# 15-100M_ClkBuffer.net
KiCad netlist of a schematic drawn in Altium Designer
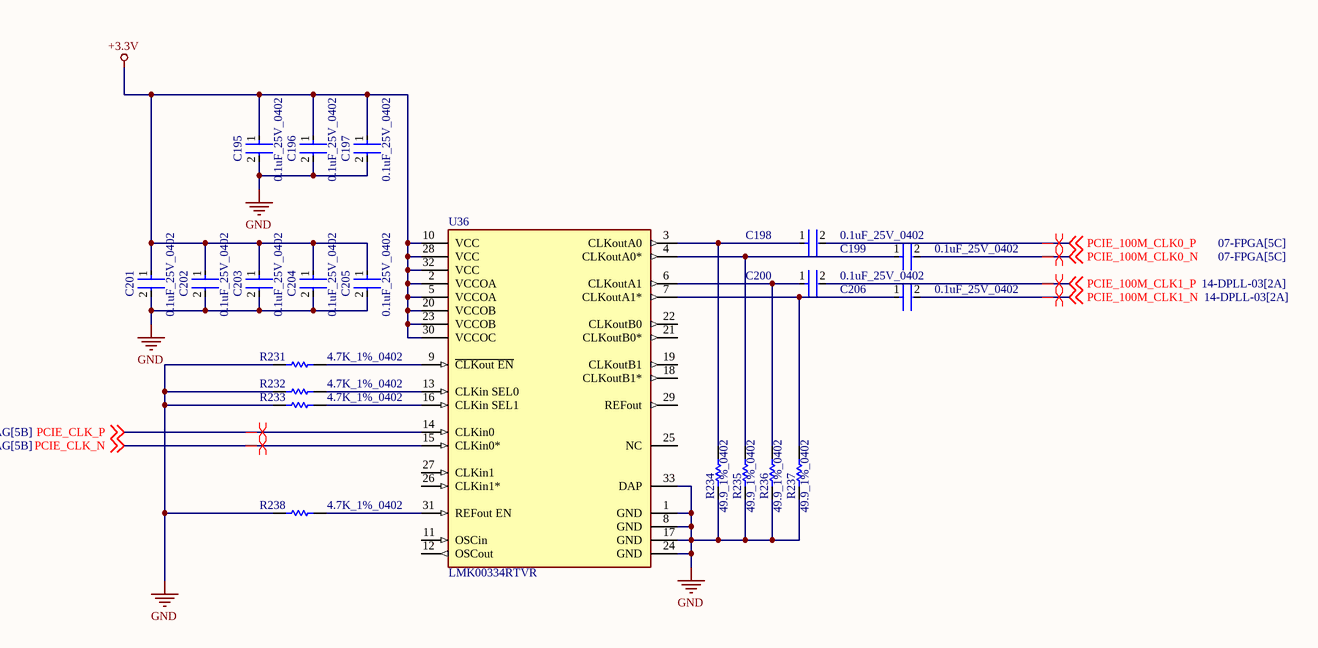
[diagram p0: 15-100M_ClkBuffer.SchDoc]

(export (version "E")
  (design (tool "Eeschema 10.0.6"))
  (components
    (comp (ref "C195")
      (value "0.1uF_25V_0402")
      (footprint "FP-0402-L_1_0_1-W_0_5_0_1-IPC_C")
      (description "General Purpose Ceramic Capacitor, 0402, 100nF, 10%, X7R, 15%, 25V")
      (fields (field (name "VOLTAGE") "25V") (field (name "TOLERANCE") "10%"))
      (libsource (lib "Altium Content Vault") (part "b4654b650e69147ec39a6b967a45e02"))
    )
    (comp (ref "C196")
      (value "0.1uF_25V_0402")
      (footprint "FP-0402-L_1_0_1-W_0_5_0_1-IPC_C")
      (description "General Purpose Ceramic Capacitor, 0402, 100nF, 10%, X7R, 15%, 25V")
      (fields (field (name "VOLTAGE") "25V") (field (name "TOLERANCE") "10%"))
      (libsource (lib "Altium Content Vault") (part "b4654b650e69147ec39a6b967a45e02"))
    )
    (comp (ref "C197")
      (value "0.1uF_25V_0402")
      (footprint "FP-0402-L_1_0_1-W_0_5_0_1-IPC_C")
      (description "General Purpose Ceramic Capacitor, 0402, 100nF, 10%, X7R, 15%, 25V")
      (fields (field (name "VOLTAGE") "25V") (field (name "TOLERANCE") "10%"))
      (libsource (lib "Altium Content Vault") (part "b4654b650e69147ec39a6b967a45e02"))
    )
    (comp (ref "C198")
      (value "0.1uF_25V_0402")
      (footprint "FP-0402-L_1_0_1-W_0_5_0_1-IPC_C")
      (description "General Purpose Ceramic Capacitor, 0402, 100nF, 10%, X7R, 15%, 25V")
      (fields (field (name "VOLTAGE") "25V") (field (name "TOLERANCE") "10%"))
      (libsource (lib "Altium Content Vault") (part "b4654b650e69147ec39a6b967a45e02"))
    )
    (comp (ref "C199")
      (value "0.1uF_25V_0402")
      (footprint "FP-0402-L_1_0_1-W_0_5_0_1-IPC_C")
      (description "General Purpose Ceramic Capacitor, 0402, 100nF, 10%, X7R, 15%, 25V")
      (fields (field (name "VOLTAGE") "25V") (field (name "TOLERANCE") "10%"))
      (libsource (lib "Altium Content Vault") (part "b4654b650e69147ec39a6b967a45e02"))
    )
    (comp (ref "C200")
      (value "0.1uF_25V_0402")
      (footprint "FP-0402-L_1_0_1-W_0_5_0_1-IPC_C")
      (description "General Purpose Ceramic Capacitor, 0402, 100nF, 10%, X7R, 15%, 25V")
      (fields (field (name "VOLTAGE") "25V") (field (name "TOLERANCE") "10%"))
      (libsource (lib "Altium Content Vault") (part "b4654b650e69147ec39a6b967a45e02"))
    )
    (comp (ref "C201")
      (value "0.1uF_25V_0402")
      (footprint "FP-0402-L_1_0_1-W_0_5_0_1-IPC_C")
      (description "General Purpose Ceramic Capacitor, 0402, 100nF, 10%, X7R, 15%, 25V")
      (fields (field (name "VOLTAGE") "25V") (field (name "TOLERANCE") "10%"))
      (libsource (lib "Altium Content Vault") (part "b4654b650e69147ec39a6b967a45e02"))
    )
    (comp (ref "C202")
      (value "0.1uF_25V_0402")
      (footprint "FP-0402-L_1_0_1-W_0_5_0_1-IPC_C")
      (description "General Purpose Ceramic Capacitor, 0402, 100nF, 10%, X7R, 15%, 25V")
      (fields (field (name "VOLTAGE") "25V") (field (name "TOLERANCE") "10%"))
      (libsource (lib "Altium Content Vault") (part "b4654b650e69147ec39a6b967a45e02"))
    )
    (comp (ref "C203")
      (value "0.1uF_25V_0402")
      (footprint "FP-0402-L_1_0_1-W_0_5_0_1-IPC_C")
      (description "General Purpose Ceramic Capacitor, 0402, 100nF, 10%, X7R, 15%, 25V")
      (fields (field (name "VOLTAGE") "25V") (field (name "TOLERANCE") "10%"))
      (libsource (lib "Altium Content Vault") (part "b4654b650e69147ec39a6b967a45e02"))
    )
    (comp (ref "C204")
      (value "0.1uF_25V_0402")
      (footprint "FP-0402-L_1_0_1-W_0_5_0_1-IPC_C")
      (description "General Purpose Ceramic Capacitor, 0402, 100nF, 10%, X7R, 15%, 25V")
      (fields (field (name "VOLTAGE") "25V") (field (name "TOLERANCE") "10%"))
      (libsource (lib "Altium Content Vault") (part "b4654b650e69147ec39a6b967a45e02"))
    )
    (comp (ref "C205")
      (value "0.1uF_25V_0402")
      (footprint "FP-0402-L_1_0_1-W_0_5_0_1-IPC_C")
      (description "General Purpose Ceramic Capacitor, 0402, 100nF, 10%, X7R, 15%, 25V")
      (fields (field (name "VOLTAGE") "25V") (field (name "TOLERANCE") "10%"))
      (libsource (lib "Altium Content Vault") (part "b4654b650e69147ec39a6b967a45e02"))
    )
    (comp (ref "C206")
      (value "0.1uF_25V_0402")
      (footprint "FP-0402-L_1_0_1-W_0_5_0_1-IPC_C")
      (description "General Purpose Ceramic Capacitor, 0402, 100nF, 10%, X7R, 15%, 25V")
      (fields (field (name "VOLTAGE") "25V") (field (name "TOLERANCE") "10%"))
      (libsource (lib "Altium Content Vault") (part "b4654b650e69147ec39a6b967a45e02"))
    )
    (comp (ref "R231")
      (value "4.7K_1%_0402")
      (footprint "RESC1005X40X25NL10T10")
      (fields (field (name "MANUFACTURER") "Bourns") (field (name "PART NUMBER") "CR0402-FX-4701GLF"))
      (libsource (lib "Altium Content Vault") (part "RES"))
    )
    (comp (ref "R232")
      (value "4.7K_1%_0402")
      (footprint "RESC1005X40X25NL10T10")
      (fields (field (name "MANUFACTURER") "Bourns") (field (name "PART NUMBER") "CR0402-FX-4701GLF"))
      (libsource (lib "Altium Content Vault") (part "RES"))
    )
    (comp (ref "R233")
      (value "4.7K_1%_0402")
      (footprint "RESC1005X40X25NL10T10")
      (fields (field (name "MANUFACTURER") "Bourns") (field (name "PART NUMBER") "CR0402-FX-4701GLF"))
      (libsource (lib "Altium Content Vault") (part "RES"))
    )
    (comp (ref "R234")
      (value "49.9_1%_0402")
      (footprint "RESC1005X40X25NL10T10")
      (fields (field (name "PART NUMBER") "RK73H1ETTP49R9F") (field (name "MANUFACTURER") "KOA Speer"))
      (libsource (lib "Altium Content Vault") (part "RES"))
    )
    (comp (ref "R235")
      (value "49.9_1%_0402")
      (footprint "RESC1005X40X25NL10T10")
      (fields (field (name "PART NUMBER") "RK73H1ETTP49R9F") (field (name "MANUFACTURER") "KOA Speer"))
      (libsource (lib "Altium Content Vault") (part "RES"))
    )
    (comp (ref "R236")
      (value "49.9_1%_0402")
      (footprint "RESC1005X40X25NL10T10")
      (fields (field (name "PART NUMBER") "RK73H1ETTP49R9F") (field (name "MANUFACTURER") "KOA Speer"))
      (libsource (lib "Altium Content Vault") (part "RES"))
    )
    (comp (ref "R237")
      (value "49.9_1%_0402")
      (footprint "RESC1005X40X25NL10T10")
      (fields (field (name "PART NUMBER") "RK73H1ETTP49R9F") (field (name "MANUFACTURER") "KOA Speer"))
      (libsource (lib "Altium Content Vault") (part "RES"))
    )
    (comp (ref "R238")
      (value "4.7K_1%_0402")
      (footprint "RESC1005X40X25NL10T10")
      (fields (field (name "MANUFACTURER") "Bourns") (field (name "PART NUMBER") "CR0402-FX-4701GLF"))
      (libsource (lib "Altium Content Vault") (part "RES"))
    )
    (comp (ref "U36")
      (value "LMK00334RTVR")
      (footprint "FP-RTV0032A-MFG")
      (description "IC CLK BUF 400MHZ 1CIRC 32WQFN")
      (libsource (lib "Altium Content Vault") (part "b0788d09999557299357136416a342e"))
    )
  )
  (nets
    (net (code "1") (name "+3.3V") (class "Default")
      (node (ref "C195") (pin "1") (pinfunction "1_1") (pintype "passive"))
      (node (ref "C196") (pin "1") (pinfunction "1_1") (pintype "passive"))
      (node (ref "C197") (pin "1") (pinfunction "1_1") (pintype "passive"))
      (node (ref "C201") (pin "1") (pinfunction "1_1") (pintype "passive"))
      (node (ref "C202") (pin "1") (pinfunction "1_1") (pintype "passive"))
      (node (ref "C203") (pin "1") (pinfunction "1_1") (pintype "passive"))
      (node (ref "C204") (pin "1") (pinfunction "1_1") (pintype "passive"))
      (node (ref "C205") (pin "1") (pinfunction "1_1") (pintype "passive"))
      (node (ref "U36") (pin "10") (pinfunction "VCC_10") (pintype "power_in"))
      (node (ref "U36") (pin "2") (pinfunction "VCCOA_2") (pintype "power_in"))
      (node (ref "U36") (pin "20") (pinfunction "VCCOB_20") (pintype "power_in"))
      (node (ref "U36") (pin "23") (pinfunction "VCCOB_23") (pintype "power_in"))
      (node (ref "U36") (pin "28") (pinfunction "VCC_28") (pintype "power_in"))
      (node (ref "U36") (pin "30") (pinfunction "VCCOC_30") (pintype "power_in"))
      (node (ref "U36") (pin "32") (pinfunction "VCC_32") (pintype "power_in"))
      (node (ref "U36") (pin "5") (pinfunction "VCCOA_5") (pintype "power_in"))
    )
    (net (code "2") (name "GND") (class "Default")
      (node (ref "C195") (pin "2") (pinfunction "2_2") (pintype "passive"))
      (node (ref "C196") (pin "2") (pinfunction "2_2") (pintype "passive"))
      (node (ref "C197") (pin "2") (pinfunction "2_2") (pintype "passive"))
      (node (ref "C201") (pin "2") (pinfunction "2_2") (pintype "passive"))
      (node (ref "C202") (pin "2") (pinfunction "2_2") (pintype "passive"))
      (node (ref "C203") (pin "2") (pinfunction "2_2") (pintype "passive"))
      (node (ref "C204") (pin "2") (pinfunction "2_2") (pintype "passive"))
      (node (ref "C205") (pin "2") (pinfunction "2_2") (pintype "passive"))
      (node (ref "R231") (pin "2") (pinfunction "2_2") (pintype "passive"))
      (node (ref "R232") (pin "2") (pinfunction "2_2") (pintype "passive"))
      (node (ref "R233") (pin "2") (pinfunction "2_2") (pintype "passive"))
      (node (ref "R234") (pin "1") (pinfunction "1_1") (pintype "passive"))
      (node (ref "R235") (pin "1") (pinfunction "1_1") (pintype "passive"))
      (node (ref "R236") (pin "1") (pinfunction "1_1") (pintype "passive"))
      (node (ref "R237") (pin "1") (pinfunction "1_1") (pintype "passive"))
      (node (ref "R238") (pin "2") (pinfunction "2_2") (pintype "passive"))
      (node (ref "U36") (pin "1") (pinfunction "GND_1") (pintype "power_in"))
      (node (ref "U36") (pin "17") (pinfunction "GND_17") (pintype "power_in"))
      (node (ref "U36") (pin "24") (pinfunction "GND_24") (pintype "power_in"))
      (node (ref "U36") (pin "33") (pinfunction "DAP_33") (pintype "power_in"))
      (node (ref "U36") (pin "8") (pinfunction "GND_8") (pintype "power_in"))
    )
    (net (code "3") (name "Net-(U36-CLKin_SEL0)") (class "Default")
      (node (ref "R232") (pin "1") (pinfunction "1_1") (pintype "passive"))
      (node (ref "U36") (pin "13") (pinfunction "CLKin_SEL0_13") (pintype "input"))
    )
    (net (code "4") (name "Net-(U36-CLKin_SEL1)") (class "Default")
      (node (ref "R233") (pin "1") (pinfunction "1_1") (pintype "passive"))
      (node (ref "U36") (pin "16") (pinfunction "CLKin_SEL1_16") (pintype "input"))
    )
    (net (code "5") (name "Net-(U36-CLKoutA0)") (class "Default")
      (node (ref "C198") (pin "1") (pinfunction "1_1") (pintype "passive"))
      (node (ref "R234") (pin "2") (pinfunction "2_2") (pintype "passive"))
      (node (ref "U36") (pin "3") (pinfunction "CLKoutA0_3") (pintype "output"))
    )
    (net (code "6") (name "Net-(U36-CLKoutA0*)") (class "Default")
      (node (ref "C199") (pin "1") (pinfunction "1_1") (pintype "passive"))
      (node (ref "R235") (pin "2") (pinfunction "2_2") (pintype "passive"))
      (node (ref "U36") (pin "4") (pinfunction "CLKoutA0*_4") (pintype "output"))
    )
    (net (code "7") (name "Net-(U36-CLKoutA1)") (class "Default")
      (node (ref "C200") (pin "1") (pinfunction "1_1") (pintype "passive"))
      (node (ref "R236") (pin "2") (pinfunction "2_2") (pintype "passive"))
      (node (ref "U36") (pin "6") (pinfunction "CLKoutA1_6") (pintype "output"))
    )
    (net (code "8") (name "Net-(U36-CLKoutA1*)") (class "Default")
      (node (ref "C206") (pin "1") (pinfunction "1_1") (pintype "passive"))
      (node (ref "R237") (pin "2") (pinfunction "2_2") (pintype "passive"))
      (node (ref "U36") (pin "7") (pinfunction "CLKoutA1*_7") (pintype "output"))
    )
    (net (code "9") (name "Net-(U36-REFout_EN)") (class "Default")
      (node (ref "R238") (pin "1") (pinfunction "1_1") (pintype "passive"))
      (node (ref "U36") (pin "31") (pinfunction "REFout_EN_31") (pintype "input"))
    )
    (net (code "10") (name "Net-(U36-~{CLKout_EN})") (class "Default")
      (node (ref "R231") (pin "1") (pinfunction "1_1") (pintype "passive"))
      (node (ref "U36") (pin "9") (pinfunction "~{CLKout_EN}_9") (pintype "input"))
    )
    (net (code "11") (name "PCIE_100M_CLK0_N") (class "Default")
      (node (ref "C199") (pin "2") (pinfunction "2_2") (pintype "passive"))
    )
    (net (code "12") (name "PCIE_100M_CLK0_P") (class "Default")
      (node (ref "C198") (pin "2") (pinfunction "2_2") (pintype "passive"))
    )
    (net (code "13") (name "PCIE_100M_CLK1_N") (class "Default")
      (node (ref "C206") (pin "2") (pinfunction "2_2") (pintype "passive"))
    )
    (net (code "14") (name "PCIE_100M_CLK1_P") (class "Default")
      (node (ref "C200") (pin "2") (pinfunction "2_2") (pintype "passive"))
    )
    (net (code "15") (name "PCIE_CLK_N") (class "Default")
      (node (ref "U36") (pin "15") (pinfunction "CLKin0*_15") (pintype "input"))
    )
    (net (code "16") (name "PCIE_CLK_P") (class "Default")
      (node (ref "U36") (pin "14") (pinfunction "CLKin0_14") (pintype "input"))
    )
    (net (code "17") (name "unconnected-(U36-CLKin1*-Pad26)") (class "Default")
      (node (ref "U36") (pin "26") (pinfunction "CLKin1*_26") (pintype "input"))
    )
    (net (code "18") (name "unconnected-(U36-CLKin1-Pad27)") (class "Default")
      (node (ref "U36") (pin "27") (pinfunction "CLKin1_27") (pintype "input"))
    )
    (net (code "19") (name "unconnected-(U36-CLKoutB0*-Pad21)") (class "Default")
      (node (ref "U36") (pin "21") (pinfunction "CLKoutB0*_21") (pintype "output"))
    )
    (net (code "20") (name "unconnected-(U36-CLKoutB0-Pad22)") (class "Default")
      (node (ref "U36") (pin "22") (pinfunction "CLKoutB0_22") (pintype "output"))
    )
    (net (code "21") (name "unconnected-(U36-CLKoutB1*-Pad18)") (class "Default")
      (node (ref "U36") (pin "18") (pinfunction "CLKoutB1*_18") (pintype "output"))
    )
    (net (code "22") (name "unconnected-(U36-CLKoutB1-Pad19)") (class "Default")
      (node (ref "U36") (pin "19") (pinfunction "CLKoutB1_19") (pintype "output"))
    )
    (net (code "23") (name "unconnected-(U36-NC-Pad25)") (class "Default")
      (node (ref "U36") (pin "25") (pinfunction "NC_25") (pintype "passive"))
    )
    (net (code "24") (name "unconnected-(U36-OSCin-Pad11)") (class "Default")
      (node (ref "U36") (pin "11") (pinfunction "OSCin_11") (pintype "input"))
    )
    (net (code "25") (name "unconnected-(U36-OSCout-Pad12)") (class "Default")
      (node (ref "U36") (pin "12") (pinfunction "OSCout_12") (pintype "output"))
    )
    (net (code "26") (name "unconnected-(U36-REFout-Pad29)") (class "Default")
      (node (ref "U36") (pin "29") (pinfunction "REFout_29") (pintype "output"))
    )
  )
)
